# LCD_TFT-Xplained_V0.net
KiCad netlist of a schematic drawn in EAGLE
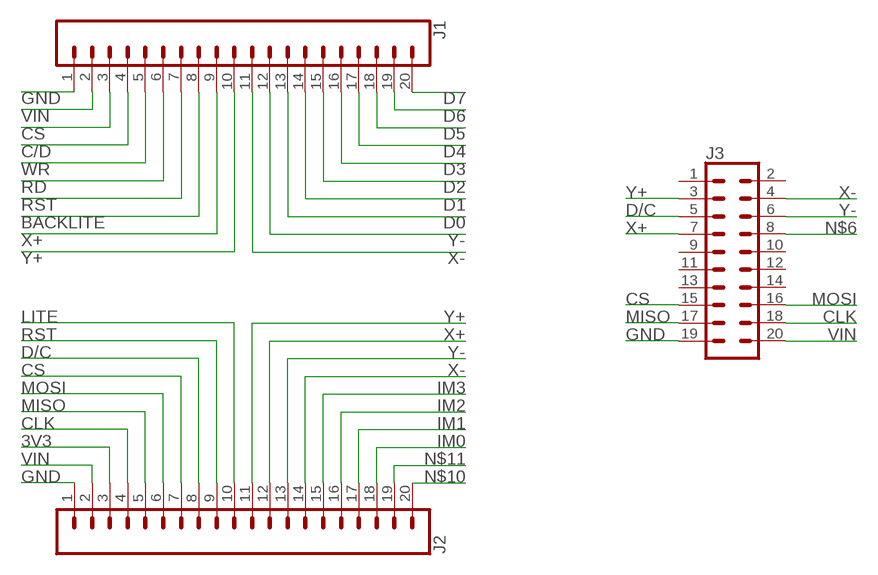
[diagram p0: schematic, sheet 1]

(export (version "E")
  (design (tool "Eeschema 10.0.6"))
  (components
    (comp (ref "J1")
      (value "CONN_20NOSILK")
      (footprint "eagle-import:1X20_NOSILK")
      (libsource (lib "eagle-import") (part "CONN_20NOSILK"))
    )
    (comp (ref "J2")
      (value "CONN_20NOSILK")
      (footprint "eagle-import:1X20_NOSILK")
      (libsource (lib "eagle-import") (part "CONN_20NOSILK"))
    )
    (comp (ref "J3")
      (value "CONN_10X2")
      (footprint "eagle-import:2X10")
      (libsource (lib "eagle-import") (part "CONN_10X2"))
    )
  )
  (nets
    (net (code "1") (name "/3V3") (class "Default")
      (node (ref "J2") (pin "3") (pinfunction "3_3") (pintype "passive"))
    )
    (net (code "2") (name "/BACKLITE") (class "Default")
      (node (ref "J1") (pin "8") (pinfunction "8_8") (pintype "passive"))
    )
    (net (code "3") (name "/CLK") (class "Default")
      (node (ref "J2") (pin "4") (pinfunction "4_4") (pintype "passive"))
      (node (ref "J3") (pin "18") (pinfunction "18_18") (pintype "passive"))
    )
    (net (code "4") (name "/CS") (class "Default")
      (node (ref "J1") (pin "3") (pinfunction "3_3") (pintype "passive"))
      (node (ref "J2") (pin "7") (pinfunction "7_7") (pintype "passive"))
      (node (ref "J3") (pin "15") (pinfunction "15_15") (pintype "passive"))
    )
    (net (code "5") (name "/C{slash}D") (class "Default")
      (node (ref "J1") (pin "4") (pinfunction "4_4") (pintype "passive"))
    )
    (net (code "6") (name "/D0") (class "Default")
      (node (ref "J1") (pin "13") (pinfunction "13_13") (pintype "passive"))
    )
    (net (code "7") (name "/D1") (class "Default")
      (node (ref "J1") (pin "14") (pinfunction "14_14") (pintype "passive"))
    )
    (net (code "8") (name "/D2") (class "Default")
      (node (ref "J1") (pin "15") (pinfunction "15_15") (pintype "passive"))
    )
    (net (code "9") (name "/D3") (class "Default")
      (node (ref "J1") (pin "16") (pinfunction "16_16") (pintype "passive"))
    )
    (net (code "10") (name "/D4") (class "Default")
      (node (ref "J1") (pin "17") (pinfunction "17_17") (pintype "passive"))
    )
    (net (code "11") (name "/D5") (class "Default")
      (node (ref "J1") (pin "18") (pinfunction "18_18") (pintype "passive"))
    )
    (net (code "12") (name "/D6") (class "Default")
      (node (ref "J1") (pin "19") (pinfunction "19_19") (pintype "passive"))
    )
    (net (code "13") (name "/D7") (class "Default")
      (node (ref "J1") (pin "20") (pinfunction "20_20") (pintype "passive"))
    )
    (net (code "14") (name "/D{slash}C") (class "Default")
      (node (ref "J2") (pin "8") (pinfunction "8_8") (pintype "passive"))
      (node (ref "J3") (pin "5") (pinfunction "5_5") (pintype "passive"))
    )
    (net (code "15") (name "/GND") (class "Default")
      (node (ref "J1") (pin "1") (pinfunction "1_1") (pintype "passive"))
      (node (ref "J2") (pin "1") (pinfunction "1_1") (pintype "passive"))
      (node (ref "J3") (pin "19") (pinfunction "19_19") (pintype "passive"))
    )
    (net (code "16") (name "/IM0") (class "Default")
      (node (ref "J2") (pin "18") (pinfunction "18_18") (pintype "passive"))
    )
    (net (code "17") (name "/IM1") (class "Default")
      (node (ref "J2") (pin "17") (pinfunction "17_17") (pintype "passive"))
    )
    (net (code "18") (name "/IM2") (class "Default")
      (node (ref "J2") (pin "16") (pinfunction "16_16") (pintype "passive"))
    )
    (net (code "19") (name "/IM3") (class "Default")
      (node (ref "J2") (pin "15") (pinfunction "15_15") (pintype "passive"))
    )
    (net (code "20") (name "/LITE") (class "Default")
      (node (ref "J2") (pin "10") (pinfunction "10_10") (pintype "passive"))
    )
    (net (code "21") (name "/MISO") (class "Default")
      (node (ref "J2") (pin "5") (pinfunction "5_5") (pintype "passive"))
      (node (ref "J3") (pin "17") (pinfunction "17_17") (pintype "passive"))
    )
    (net (code "22") (name "/MOSI") (class "Default")
      (node (ref "J2") (pin "6") (pinfunction "6_6") (pintype "passive"))
      (node (ref "J3") (pin "16") (pinfunction "16_16") (pintype "passive"))
    )
    (net (code "23") (name "/N$6") (class "Default")
      (node (ref "J3") (pin "8") (pinfunction "8_8") (pintype "passive"))
    )
    (net (code "24") (name "/N$10") (class "Default")
      (node (ref "J2") (pin "20") (pinfunction "20_20") (pintype "passive"))
    )
    (net (code "25") (name "/N$11") (class "Default")
      (node (ref "J2") (pin "19") (pinfunction "19_19") (pintype "passive"))
    )
    (net (code "26") (name "/RD") (class "Default")
      (node (ref "J1") (pin "6") (pinfunction "6_6") (pintype "passive"))
    )
    (net (code "27") (name "/RST") (class "Default")
      (node (ref "J1") (pin "7") (pinfunction "7_7") (pintype "passive"))
      (node (ref "J2") (pin "9") (pinfunction "9_9") (pintype "passive"))
    )
    (net (code "28") (name "/VIN") (class "Default")
      (node (ref "J1") (pin "2") (pinfunction "2_2") (pintype "passive"))
      (node (ref "J2") (pin "2") (pinfunction "2_2") (pintype "passive"))
      (node (ref "J3") (pin "20") (pinfunction "20_20") (pintype "passive"))
    )
    (net (code "29") (name "/WR") (class "Default")
      (node (ref "J1") (pin "5") (pinfunction "5_5") (pintype "passive"))
    )
    (net (code "30") (name "/X+") (class "Default")
      (node (ref "J1") (pin "9") (pinfunction "9_9") (pintype "passive"))
      (node (ref "J2") (pin "12") (pinfunction "12_12") (pintype "passive"))
      (node (ref "J3") (pin "7") (pinfunction "7_7") (pintype "passive"))
    )
    (net (code "31") (name "/X-") (class "Default")
      (node (ref "J1") (pin "11") (pinfunction "11_11") (pintype "passive"))
      (node (ref "J2") (pin "14") (pinfunction "14_14") (pintype "passive"))
      (node (ref "J3") (pin "4") (pinfunction "4_4") (pintype "passive"))
    )
    (net (code "32") (name "/Y+") (class "Default")
      (node (ref "J1") (pin "10") (pinfunction "10_10") (pintype "passive"))
      (node (ref "J2") (pin "11") (pinfunction "11_11") (pintype "passive"))
      (node (ref "J3") (pin "3") (pinfunction "3_3") (pintype "passive"))
    )
    (net (code "33") (name "/Y-") (class "Default")
      (node (ref "J1") (pin "12") (pinfunction "12_12") (pintype "passive"))
      (node (ref "J2") (pin "13") (pinfunction "13_13") (pintype "passive"))
      (node (ref "J3") (pin "6") (pinfunction "6_6") (pintype "passive"))
    )
    (net (code "34") (name "unconnected-(J3-Pad1)") (class "Default")
      (node (ref "J3") (pin "1") (pinfunction "1_1") (pintype "passive"))
    )
    (net (code "35") (name "unconnected-(J3-Pad2)") (class "Default")
      (node (ref "J3") (pin "2") (pinfunction "2_2") (pintype "passive"))
    )
    (net (code "36") (name "unconnected-(J3-Pad9)") (class "Default")
      (node (ref "J3") (pin "9") (pinfunction "9_9") (pintype "passive"))
    )
    (net (code "37") (name "unconnected-(J3-Pad10)") (class "Default")
      (node (ref "J3") (pin "10") (pinfunction "10_10") (pintype "passive"))
    )
    (net (code "38") (name "unconnected-(J3-Pad11)") (class "Default")
      (node (ref "J3") (pin "11") (pinfunction "11_11") (pintype "passive"))
    )
    (net (code "39") (name "unconnected-(J3-Pad12)") (class "Default")
      (node (ref "J3") (pin "12") (pinfunction "12_12") (pintype "passive"))
    )
    (net (code "40") (name "unconnected-(J3-Pad13)") (class "Default")
      (node (ref "J3") (pin "13") (pinfunction "13_13") (pintype "passive"))
    )
    (net (code "41") (name "unconnected-(J3-Pad14)") (class "Default")
      (node (ref "J3") (pin "14") (pinfunction "14_14") (pintype "passive"))
    )
  )
)
